# charge_board_v4-5.net
KiCad netlist of a schematic drawn in EAGLE
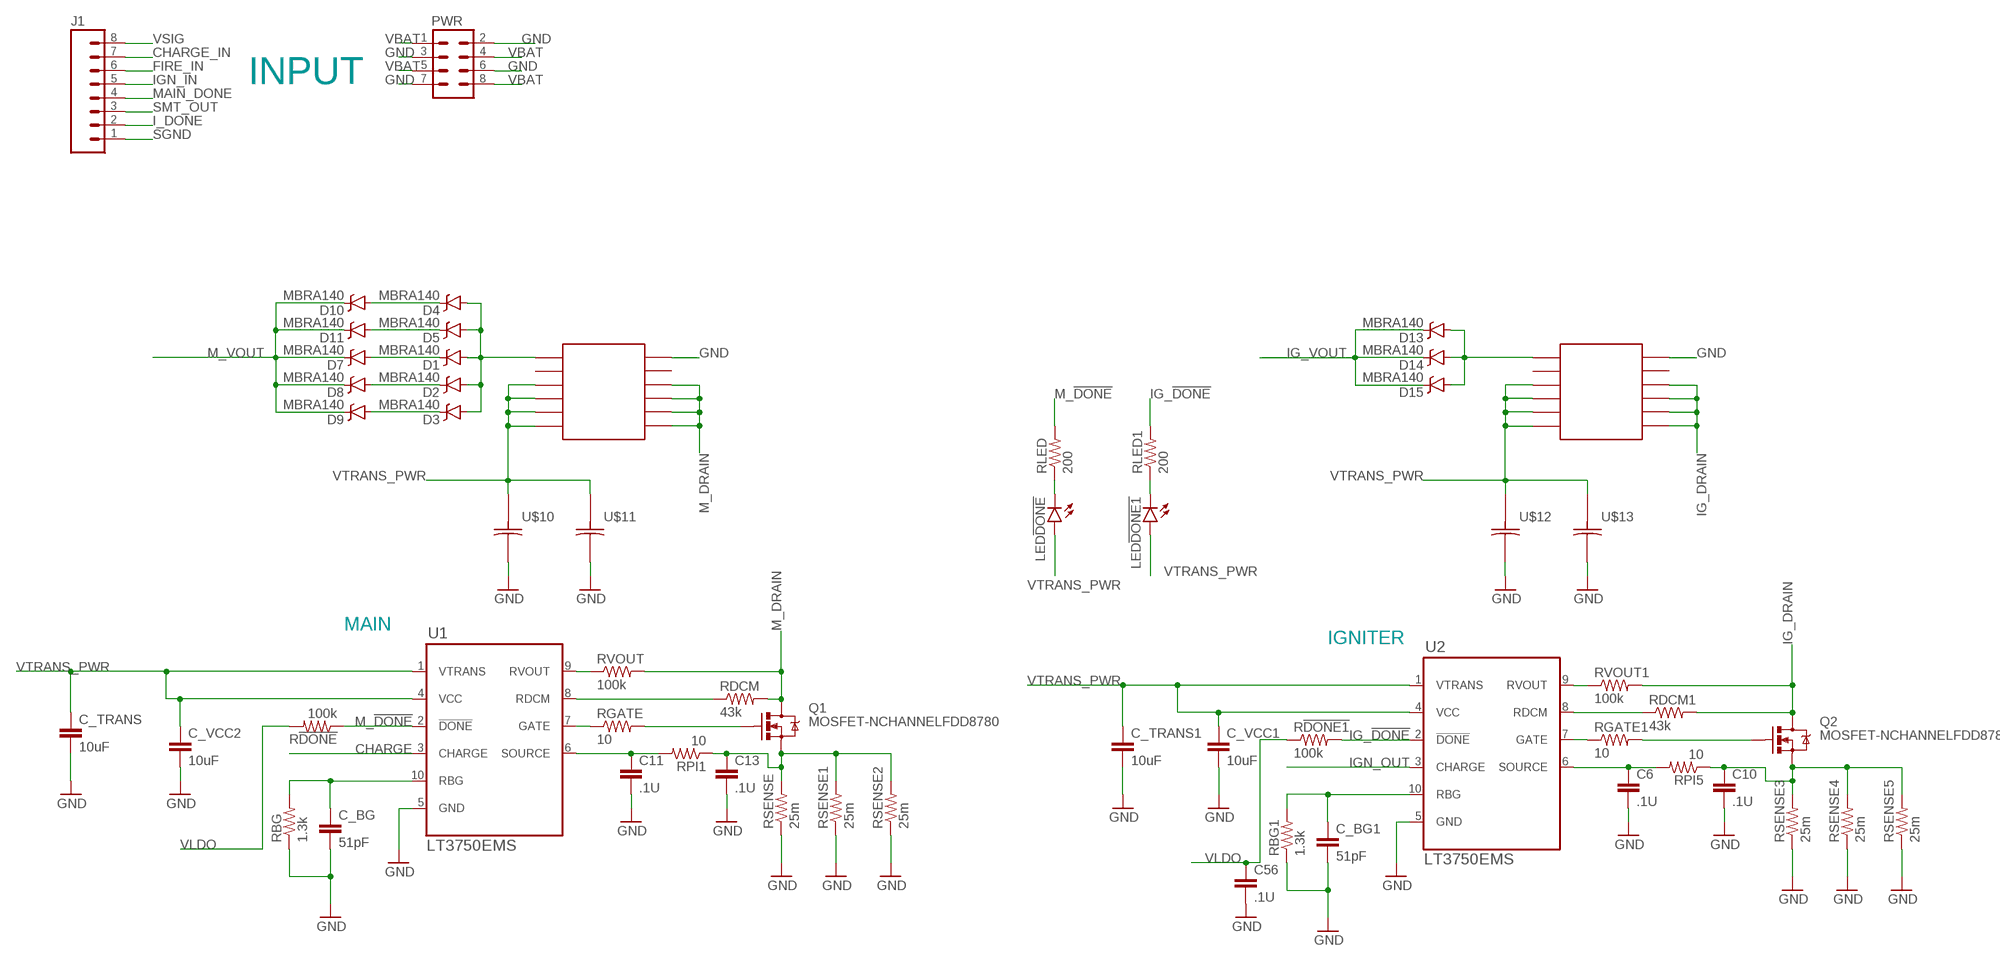
[diagram p0: schematic, sheet 1]
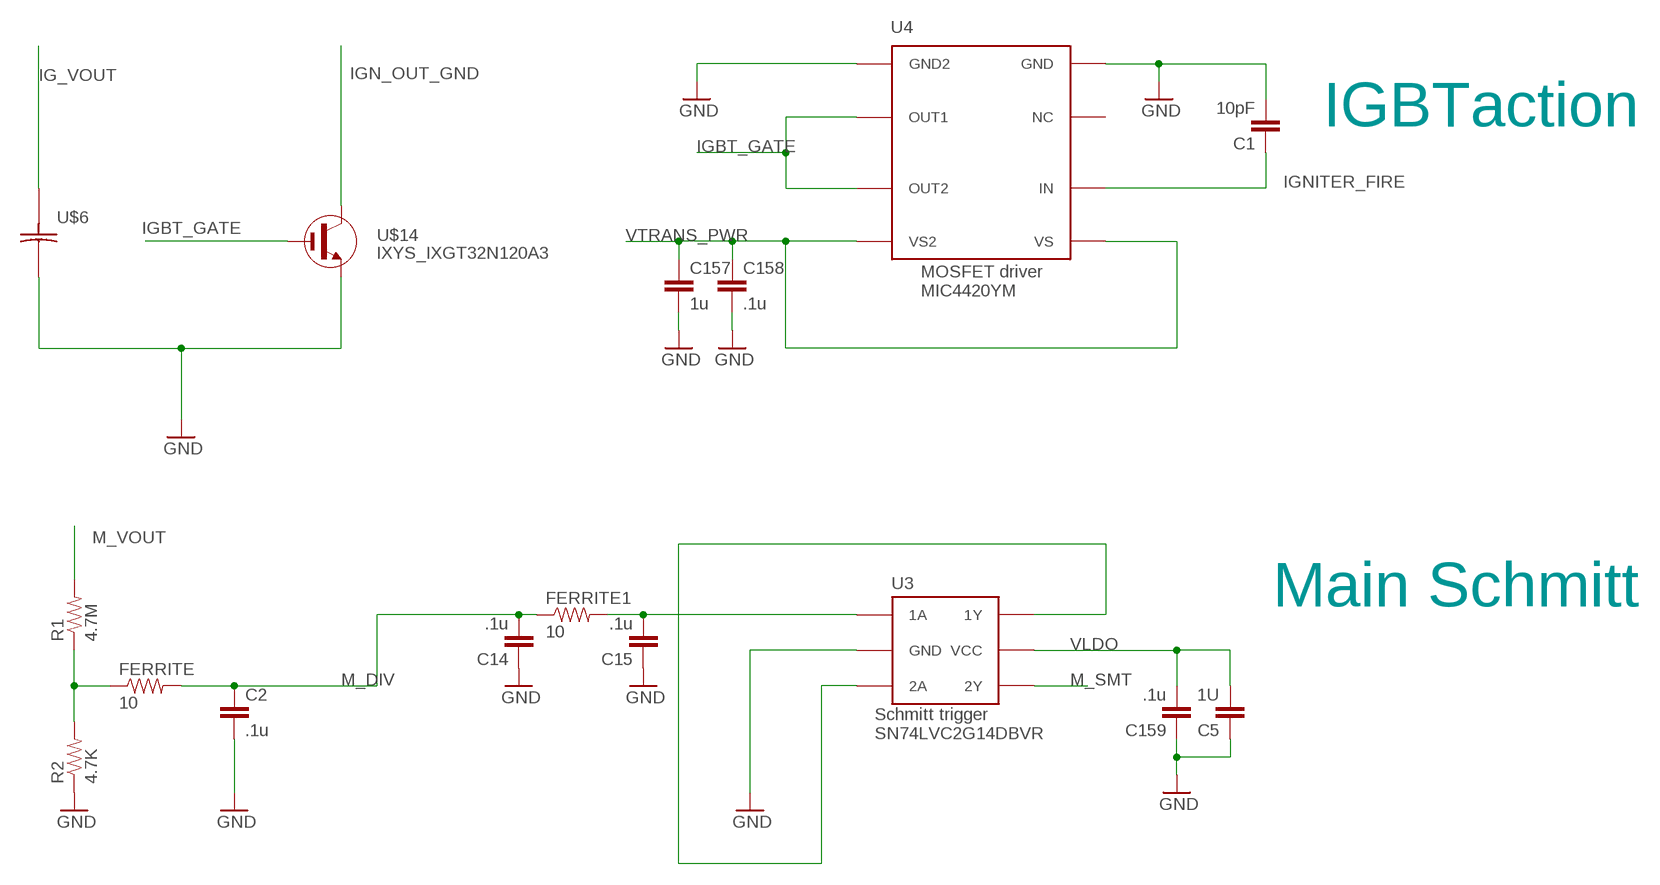
[diagram p1: schematic, sheet 2]
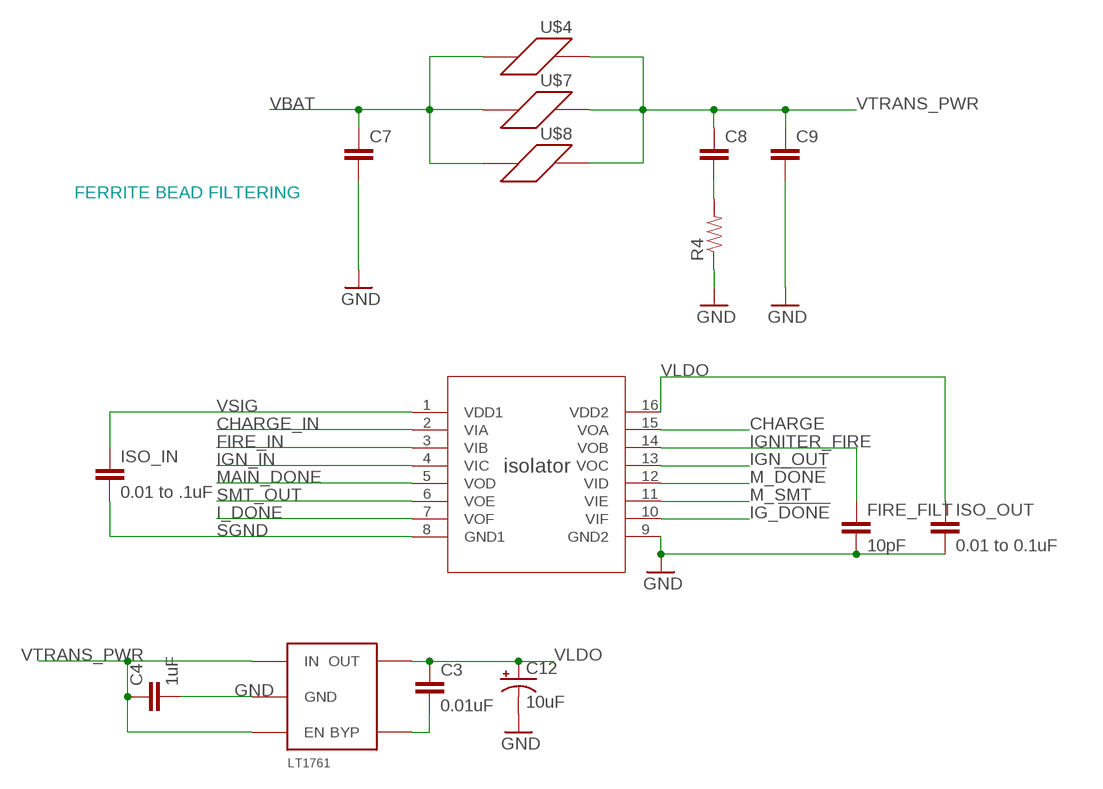
[diagram p2: schematic, sheet 3]

(export (version "E")
  (design (tool "Eeschema 10.0.6"))
  (components
    (comp (ref "C1")
      (value "10pF")
      (footprint "eagle-import:0805")
      (libsource (lib "eagle-import") (part "CAP0805"))
    )
    (comp (ref "C2")
      (value ".1u")
      (footprint "eagle-import:0805")
      (libsource (lib "eagle-import") (part "CAP0805"))
    )
    (comp (ref "C5")
      (value "1U")
      (footprint "eagle-import:0805")
      (libsource (lib "eagle-import") (part "CAP0805"))
    )
    (comp (ref "C14")
      (value ".1u")
      (footprint "eagle-import:0805")
      (libsource (lib "eagle-import") (part "CAP0805"))
    )
    (comp (ref "C15")
      (value ".1u")
      (footprint "eagle-import:0805")
      (libsource (lib "eagle-import") (part "CAP0805"))
    )
    (comp (ref "C157")
      (value "1u")
      (footprint "eagle-import:0805")
      (libsource (lib "eagle-import") (part "CAP0805"))
    )
    (comp (ref "C158")
      (value ".1u")
      (footprint "eagle-import:0805")
      (libsource (lib "eagle-import") (part "CAP0805"))
    )
    (comp (ref "C159")
      (value ".1u")
      (footprint "eagle-import:0805")
      (libsource (lib "eagle-import") (part "CAP0805"))
    )
    (comp (ref "FERRITE")
      (value "10")
      (footprint "eagle-import:0805")
      (libsource (lib "eagle-import") (part "RESISTOR0805-RES"))
    )
    (comp (ref "FERRITE1")
      (value "10")
      (footprint "eagle-import:0805")
      (libsource (lib "eagle-import") (part "RESISTOR0805-RES"))
    )
    (comp (ref "R1")
      (value "4.7M")
      (footprint "eagle-import:R2010")
      (libsource (lib "eagle-import") (part "RESISTOR2010"))
    )
    (comp (ref "R2")
      (value "4.7K")
      (footprint "eagle-import:R2010")
      (libsource (lib "eagle-import") (part "RESISTOR2010"))
    )
    (comp (ref "U$6")
      (value "KEMET_LDEQH3100KA5N00")
      (footprint "eagle-import:KEMET_F3078")
      (libsource (lib "eagle-import") (part "KEMET_LDEQH3100KA5N00"))
    )
    (comp (ref "U$14")
      (value "IXYS_IXGT32N120A3")
      (footprint "eagle-import:TO-268")
      (libsource (lib "eagle-import") (part "IXYS_IXGT32N120A3"))
    )
    (comp (ref "U3")
      (value "TI_SCHMITTRIGGER_SN74")
      (footprint "eagle-import:SOT-23-6")
      (libsource (lib "eagle-import") (part "TI_SCHMITTRIGGER_SN74"))
    )
    (comp (ref "U4")
      (value "MICREL_MOSFETDRIVER_MIC4420")
      (footprint "eagle-import:8-SOIC")
      (libsource (lib "eagle-import") (part "MICREL_MOSFETDRIVER_MIC4420"))
    )
    (comp (ref "ADUM163N")
      (value "ADUM163N1BRZ")
      (footprint "eagle-import:R_16")
      (libsource (lib "eagle-import") (part "ADUM163N1BRZ"))
    )
    (comp (ref "C3")
      (value "0.01uF")
      (footprint "eagle-import:0805")
      (libsource (lib "eagle-import") (part "SparkFun-Passives_CAP0805"))
    )
    (comp (ref "C4")
      (value "1uF")
      (footprint "eagle-import:0805")
      (libsource (lib "eagle-import") (part "SparkFun-Passives_CAP0805"))
    )
    (comp (ref "C7")
      (value "CAP0805")
      (footprint "eagle-import:0805")
      (libsource (lib "eagle-import") (part "CAP0805"))
    )
    (comp (ref "C8")
      (value "CAP0805")
      (footprint "eagle-import:0805")
      (libsource (lib "eagle-import") (part "CAP0805"))
    )
    (comp (ref "C9")
      (value "CAP0805")
      (footprint "eagle-import:0805")
      (libsource (lib "eagle-import") (part "CAP0805"))
    )
    (comp (ref "C12")
      (value "10uF")
      (footprint "eagle-import:EIA3216")
      (libsource (lib "eagle-import") (part "10UF-TANT"))
    )
    (comp (ref "FIRE_FILT")
      (value "10pF")
      (footprint "eagle-import:0805")
      (libsource (lib "eagle-import") (part "SparkFun-Passives_CAP0805"))
    )
    (comp (ref "ISO_IN")
      (value "0.01 to .1uF")
      (footprint "eagle-import:0805")
      (libsource (lib "eagle-import") (part "SparkFun-Passives_CAP0805"))
    )
    (comp (ref "ISO_OUT")
      (value "0.01 to 0.1uF")
      (footprint "eagle-import:0805")
      (libsource (lib "eagle-import") (part "SparkFun-Passives_CAP0805"))
    )
    (comp (ref "LDO")
      (value "LINEAR_LDO_LT1761-X")
      (footprint "eagle-import:SOT-23-5")
      (libsource (lib "eagle-import") (part "LINEAR_LDO_LT1761-X"))
    )
    (comp (ref "R4")
      (value "RESISTOR0805-RES")
      (footprint "eagle-import:0805")
      (libsource (lib "eagle-import") (part "RESISTOR0805-RES"))
    )
    (comp (ref "U$4")
      (value "B.L1_FBMJ2125HS420-T")
      (footprint "eagle-import:0805")
      (libsource (lib "eagle-import") (part "B.L1_FBMJ2125HS420-T"))
    )
    (comp (ref "U$7")
      (value "B.L2_FBMH1608HL121-T")
      (footprint "eagle-import:0603")
      (libsource (lib "eagle-import") (part "B.L2_FBMH1608HL121-T"))
    )
    (comp (ref "U$8")
      (value "I.L1_587-3855-1-ND")
      (footprint "eagle-import:1206")
      (libsource (lib "eagle-import") (part "I.L1_587-3855-1-ND"))
    )
    (comp (ref "C6")
      (value ".1U")
      (footprint "eagle-import:0805")
      (libsource (lib "eagle-import") (part "CAP0805"))
    )
    (comp (ref "C10")
      (value ".1U")
      (footprint "eagle-import:0805")
      (libsource (lib "eagle-import") (part "CAP0805"))
    )
    (comp (ref "C11")
      (value ".1U")
      (footprint "eagle-import:0805")
      (libsource (lib "eagle-import") (part "CAP0805"))
    )
    (comp (ref "C13")
      (value ".1U")
      (footprint "eagle-import:0805")
      (libsource (lib "eagle-import") (part "CAP0805"))
    )
    (comp (ref "C56")
      (value ".1U")
      (footprint "eagle-import:0805")
      (libsource (lib "eagle-import") (part "CAP0805"))
    )
    (comp (ref "C_BG")
      (value "51pF")
      (footprint "eagle-import:0805")
      (libsource (lib "eagle-import") (part "CAP0805"))
    )
    (comp (ref "C_BG1")
      (value "51pF")
      (footprint "eagle-import:0805")
      (libsource (lib "eagle-import") (part "CAP0805"))
    )
    (comp (ref "C_TRANS")
      (value "10uF")
      (footprint "eagle-import:0805")
      (libsource (lib "eagle-import") (part "CAP0805"))
    )
    (comp (ref "C_TRANS1")
      (value "10uF")
      (footprint "eagle-import:0805")
      (libsource (lib "eagle-import") (part "CAP0805"))
    )
    (comp (ref "C_VCC1")
      (value "10uF")
      (footprint "eagle-import:0805")
      (libsource (lib "eagle-import") (part "CAP0805"))
    )
    (comp (ref "C_VCC2")
      (value "10uF")
      (footprint "eagle-import:0805")
      (libsource (lib "eagle-import") (part "CAP0805"))
    )
    (comp (ref "D1")
      (value "MBRA140")
      (footprint "eagle-import:SMA-DIODE")
      (libsource (lib "eagle-import") (part "MBRA140"))
    )
    (comp (ref "D2")
      (value "MBRA140")
      (footprint "eagle-import:SMA-DIODE")
      (libsource (lib "eagle-import") (part "MBRA140"))
    )
    (comp (ref "D3")
      (value "MBRA140")
      (footprint "eagle-import:SMA-DIODE")
      (libsource (lib "eagle-import") (part "MBRA140"))
    )
    (comp (ref "D4")
      (value "MBRA140")
      (footprint "eagle-import:SMA-DIODE")
      (libsource (lib "eagle-import") (part "MBRA140"))
    )
    (comp (ref "D5")
      (value "MBRA140")
      (footprint "eagle-import:SMA-DIODE")
      (libsource (lib "eagle-import") (part "MBRA140"))
    )
    (comp (ref "D7")
      (value "MBRA140")
      (footprint "eagle-import:SMA-DIODE")
      (libsource (lib "eagle-import") (part "MBRA140"))
    )
    (comp (ref "D8")
      (value "MBRA140")
      (footprint "eagle-import:SMA-DIODE")
      (libsource (lib "eagle-import") (part "MBRA140"))
    )
    (comp (ref "D9")
      (value "MBRA140")
      (footprint "eagle-import:SMA-DIODE")
      (libsource (lib "eagle-import") (part "MBRA140"))
    )
    (comp (ref "D10")
      (value "MBRA140")
      (footprint "eagle-import:SMA-DIODE")
      (libsource (lib "eagle-import") (part "MBRA140"))
    )
    (comp (ref "D11")
      (value "MBRA140")
      (footprint "eagle-import:SMA-DIODE")
      (libsource (lib "eagle-import") (part "MBRA140"))
    )
    (comp (ref "D13")
      (value "MBRA140")
      (footprint "eagle-import:SMA-DIODE")
      (libsource (lib "eagle-import") (part "MBRA140"))
    )
    (comp (ref "D14")
      (value "MBRA140")
      (footprint "eagle-import:SMA-DIODE")
      (libsource (lib "eagle-import") (part "MBRA140"))
    )
    (comp (ref "D15")
      (value "MBRA140")
      (footprint "eagle-import:SMA-DIODE")
      (libsource (lib "eagle-import") (part "MBRA140"))
    )
    (comp (ref "J1")
      (value "M08")
      (footprint "eagle-import:1X08_ROUND")
      (libsource (lib "eagle-import") (part "M08"))
    )
    (comp (ref "LED!DONE")
      (value "LED1206")
      (footprint "eagle-import:LED-1206")
      (libsource (lib "eagle-import") (part "LED1206"))
    )
    (comp (ref "LED!DONE1")
      (value "LED1206")
      (footprint "eagle-import:LED-1206")
      (libsource (lib "eagle-import") (part "LED1206"))
    )
    (comp (ref "PWR")
      (value "M04X2")
      (footprint "eagle-import:2X4")
      (libsource (lib "eagle-import") (part "M04X2"))
    )
    (comp (ref "Q1")
      (value "MOSFET-NCHANNELFDD8780")
      (footprint "eagle-import:DPAK")
      (libsource (lib "eagle-import") (part "MOSFET-NCHANNELFDD8780"))
    )
    (comp (ref "Q2")
      (value "MOSFET-NCHANNELFDD8780")
      (footprint "eagle-import:DPAK")
      (libsource (lib "eagle-import") (part "MOSFET-NCHANNELFDD8780"))
    )
    (comp (ref "R!DONE")
      (value "100k")
      (footprint "eagle-import:0805")
      (libsource (lib "eagle-import") (part "SparkFun-Resistors_RESISTOR0805-RES"))
    )
    (comp (ref "R!DONE1")
      (value "100k")
      (footprint "eagle-import:0805")
      (libsource (lib "eagle-import") (part "SparkFun-Resistors_RESISTOR0805-RES"))
    )
    (comp (ref "RBG")
      (value "1.3k")
      (footprint "eagle-import:0805")
      (libsource (lib "eagle-import") (part "SparkFun-Resistors_RESISTOR0805-RES"))
    )
    (comp (ref "RBG1")
      (value "1.3k")
      (footprint "eagle-import:0805")
      (libsource (lib "eagle-import") (part "SparkFun-Resistors_RESISTOR0805-RES"))
    )
    (comp (ref "RDCM")
      (value "43k")
      (footprint "eagle-import:0805")
      (libsource (lib "eagle-import") (part "SparkFun-Resistors_RESISTOR0805-RES"))
    )
    (comp (ref "RDCM1")
      (value "43k")
      (footprint "eagle-import:0805")
      (libsource (lib "eagle-import") (part "SparkFun-Resistors_RESISTOR0805-RES"))
    )
    (comp (ref "RGATE")
      (value "10")
      (footprint "eagle-import:0805")
      (libsource (lib "eagle-import") (part "SparkFun-Resistors_RESISTOR0805-RES"))
    )
    (comp (ref "RGATE1")
      (value "10")
      (footprint "eagle-import:0805")
      (libsource (lib "eagle-import") (part "SparkFun-Resistors_RESISTOR0805-RES"))
    )
    (comp (ref "RLED")
      (value "200")
      (footprint "eagle-import:0805")
      (libsource (lib "eagle-import") (part "RESISTOR0805-RES"))
    )
    (comp (ref "RLED1")
      (value "200")
      (footprint "eagle-import:0805")
      (libsource (lib "eagle-import") (part "RESISTOR0805-RES"))
    )
    (comp (ref "RPI1")
      (value "10")
      (footprint "eagle-import:0805")
      (libsource (lib "eagle-import") (part "SparkFun-Resistors_RESISTOR0805-RES"))
    )
    (comp (ref "RPI5")
      (value "10")
      (footprint "eagle-import:0805")
      (libsource (lib "eagle-import") (part "SparkFun-Resistors_RESISTOR0805-RES"))
    )
    (comp (ref "RSENSE")
      (value "25m")
      (footprint "eagle-import:0805")
      (libsource (lib "eagle-import") (part "SparkFun-Resistors_RESISTOR0805-RES"))
    )
    (comp (ref "RSENSE1")
      (value "25m")
      (footprint "eagle-import:0805")
      (libsource (lib "eagle-import") (part "SparkFun-Resistors_RESISTOR0805-RES"))
    )
    (comp (ref "RSENSE2")
      (value "25m")
      (footprint "eagle-import:0805")
      (libsource (lib "eagle-import") (part "SparkFun-Resistors_RESISTOR0805-RES"))
    )
    (comp (ref "RSENSE3")
      (value "25m")
      (footprint "eagle-import:0805")
      (libsource (lib "eagle-import") (part "SparkFun-Resistors_RESISTOR0805-RES"))
    )
    (comp (ref "RSENSE4")
      (value "25m")
      (footprint "eagle-import:0805")
      (libsource (lib "eagle-import") (part "SparkFun-Resistors_RESISTOR0805-RES"))
    )
    (comp (ref "RSENSE5")
      (value "25m")
      (footprint "eagle-import:0805")
      (libsource (lib "eagle-import") (part "SparkFun-Resistors_RESISTOR0805-RES"))
    )
    (comp (ref "RVOUT")
      (value "100k")
      (footprint "eagle-import:0805")
      (libsource (lib "eagle-import") (part "SparkFun-Resistors_RESISTOR0805-RES"))
    )
    (comp (ref "RVOUT1")
      (value "100k")
      (footprint "eagle-import:0805")
      (libsource (lib "eagle-import") (part "SparkFun-Resistors_RESISTOR0805-RES"))
    )
    (comp (ref "U$1")
      (value "COILCRAFT_DA2034")
      (footprint "eagle-import:DA2034")
      (libsource (lib "eagle-import") (part "COILCRAFT_DA2034"))
    )
    (comp (ref "U$2")
      (value "COILCRAFT_DA2033")
      (footprint "eagle-import:DA2033")
      (libsource (lib "eagle-import") (part "COILCRAFT_DA2033"))
    )
    (comp (ref "U$10")
      (value "PANASONIC_16SVPG270M")
      (footprint "eagle-import:PANASONIC_SVPG")
      (libsource (lib "eagle-import") (part "PANASONIC_16SVPG270M"))
    )
    (comp (ref "U$11")
      (value "PANASONIC_16SVPG270M")
      (footprint "eagle-import:PANASONIC_SVPG")
      (libsource (lib "eagle-import") (part "PANASONIC_16SVPG270M"))
    )
    (comp (ref "U$12")
      (value "PANASONIC_16SVPG270M")
      (footprint "eagle-import:PANASONIC_SVPG")
      (libsource (lib "eagle-import") (part "PANASONIC_16SVPG270M"))
    )
    (comp (ref "U$13")
      (value "PANASONIC_16SVPG270M")
      (footprint "eagle-import:PANASONIC_SVPG")
      (libsource (lib "eagle-import") (part "PANASONIC_16SVPG270M"))
    )
    (comp (ref "U1")
      (value "LT3750EMS")
      (footprint "eagle-import:MSOP10")
      (libsource (lib "eagle-import") (part "LT3750EMS"))
    )
    (comp (ref "U2")
      (value "LT3750EMS")
      (footprint "eagle-import:MSOP10")
      (libsource (lib "eagle-import") (part "LT3750EMS"))
    )
  )
  (nets
    (net (code "1") (name "CHARGE") (class "Default")
      (node (ref "ADUM163N") (pin "15") (pinfunction "VOA_15") (pintype "passive"))
      (node (ref "U1") (pin "3") (pinfunction "CHARGE_3") (pintype "bidirectional"))
    )
    (net (code "2") (name "CHARGE_IN") (class "Default")
      (node (ref "ADUM163N") (pin "2") (pinfunction "VIA_2") (pintype "passive"))
      (node (ref "J1") (pin "7") (pinfunction "7_7") (pintype "passive"))
    )
    (net (code "3") (name "FIRE_IN") (class "Default")
      (node (ref "ADUM163N") (pin "3") (pinfunction "VIB_3") (pintype "passive"))
      (node (ref "J1") (pin "6") (pinfunction "6_6") (pintype "passive"))
    )
    (net (code "4") (name "GND") (class "Default")
      (node (ref "ADUM163N") (pin "9") (pinfunction "GND2_9") (pintype "passive"))
      (node (ref "C1") (pin "2") (pinfunction "2_2") (pintype "passive"))
      (node (ref "C10") (pin "2") (pinfunction "2_2") (pintype "passive"))
      (node (ref "C11") (pin "2") (pinfunction "2_2") (pintype "passive"))
      (node (ref "C12") (pin "C") (pinfunction "-_C") (pintype "passive"))
      (node (ref "C13") (pin "2") (pinfunction "2_2") (pintype "passive"))
      (node (ref "C14") (pin "1") (pinfunction "1_1") (pintype "passive"))
      (node (ref "C15") (pin "1") (pinfunction "1_1") (pintype "passive"))
      (node (ref "C157") (pin "2") (pinfunction "2_2") (pintype "passive"))
      (node (ref "C158") (pin "2") (pinfunction "2_2") (pintype "passive"))
      (node (ref "C159") (pin "1") (pinfunction "1_1") (pintype "passive"))
      (node (ref "C2") (pin "2") (pinfunction "2_2") (pintype "passive"))
      (node (ref "C4") (pin "2") (pinfunction "2_2") (pintype "passive"))
      (node (ref "C5") (pin "1") (pinfunction "1_1") (pintype "passive"))
      (node (ref "C56") (pin "2") (pinfunction "2_2") (pintype "passive"))
      (node (ref "C6") (pin "2") (pinfunction "2_2") (pintype "passive"))
      (node (ref "C7") (pin "2") (pinfunction "2_2") (pintype "passive"))
      (node (ref "C9") (pin "2") (pinfunction "2_2") (pintype "passive"))
      (node (ref "C_BG") (pin "2") (pinfunction "2_2") (pintype "passive"))
      (node (ref "C_BG1") (pin "2") (pinfunction "2_2") (pintype "passive"))
      (node (ref "C_TRANS") (pin "2") (pinfunction "2_2") (pintype "passive"))
      (node (ref "C_TRANS1") (pin "2") (pinfunction "2_2") (pintype "passive"))
      (node (ref "C_VCC1") (pin "2") (pinfunction "2_2") (pintype "passive"))
      (node (ref "C_VCC2") (pin "2") (pinfunction "2_2") (pintype "passive"))
      (node (ref "FIRE_FILT") (pin "2") (pinfunction "2_2") (pintype "passive"))
      (node (ref "ISO_OUT") (pin "2") (pinfunction "2_2") (pintype "passive"))
      (node (ref "LDO") (pin "P$2") (pinfunction "GND_P$2") (pintype "bidirectional"))
      (node (ref "PWR") (pin "2") (pinfunction "2_2") (pintype "passive"))
      (node (ref "PWR") (pin "3") (pinfunction "3_3") (pintype "passive"))
      (node (ref "PWR") (pin "6") (pinfunction "6_6") (pintype "passive"))
      (node (ref "PWR") (pin "7") (pinfunction "7_7") (pintype "passive"))
      (node (ref "R2") (pin "1") (pinfunction "1_1") (pintype "passive"))
      (node (ref "R4") (pin "1") (pinfunction "1_1") (pintype "passive"))
      (node (ref "RBG") (pin "1") (pinfunction "1_1") (pintype "passive"))
      (node (ref "RBG1") (pin "1") (pinfunction "1_1") (pintype "passive"))
      (node (ref "RSENSE") (pin "1") (pinfunction "1_1") (pintype "passive"))
      (node (ref "RSENSE1") (pin "1") (pinfunction "1_1") (pintype "passive"))
      (node (ref "RSENSE2") (pin "1") (pinfunction "1_1") (pintype "passive"))
      (node (ref "RSENSE3") (pin "1") (pinfunction "1_1") (pintype "passive"))
      (node (ref "RSENSE4") (pin "1") (pinfunction "1_1") (pintype "passive"))
      (node (ref "RSENSE5") (pin "1") (pinfunction "1_1") (pintype "passive"))
      (node (ref "U$1") (pin "P$12") (pinfunction "P$12_P$12") (pintype "bidirectional"))
      (node (ref "U$10") (pin "NEG") (pinfunction "NEG_NEG") (pintype "bidirectional"))
      (node (ref "U$11") (pin "NEG") (pinfunction "NEG_NEG") (pintype "bidirectional"))
      (node (ref "U$12") (pin "NEG") (pinfunction "NEG_NEG") (pintype "bidirectional"))
      (node (ref "U$13") (pin "NEG") (pinfunction "NEG_NEG") (pintype "bidirectional"))
      (node (ref "U$14") (pin "3") (pinfunction "E_3") (pintype "passive"))
      (node (ref "U$2") (pin "P$12") (pinfunction "P$12_P$12") (pintype "bidirectional"))
      (node (ref "U$6") (pin "NEG") (pinfunction "NEG_NEG") (pintype "bidirectional"))
      (node (ref "U1") (pin "5") (pinfunction "GND_5") (pintype "passive"))
      (node (ref "U2") (pin "5") (pinfunction "GND_5") (pintype "passive"))
      (node (ref "U3") (pin "P$2") (pinfunction "GND_P$2") (pintype "bidirectional"))
      (node (ref "U4") (pin "P$4") (pinfunction "GND_P$4") (pintype "bidirectional"))
      (node (ref "U4") (pin "P$5") (pinfunction "GND2_P$5") (pintype "bidirectional"))
    )
    (net (code "5") (name "IGBT_GATE") (class "Default")
      (node (ref "U$14") (pin "1") (pinfunction "G_1") (pintype "passive"))
      (node (ref "U4") (pin "P$6") (pinfunction "OUT1_P$6") (pintype "bidirectional"))
      (node (ref "U4") (pin "P$7") (pinfunction "OUT2_P$7") (pintype "bidirectional"))
    )
    (net (code "6") (name "IGNITER_FIRE") (class "Default")
      (node (ref "ADUM163N") (pin "14") (pinfunction "VOB_14") (pintype "passive"))
      (node (ref "C1") (pin "1") (pinfunction "1_1") (pintype "passive"))
      (node (ref "FIRE_FILT") (pin "1") (pinfunction "1_1") (pintype "passive"))
      (node (ref "U4") (pin "P$2") (pinfunction "IN_P$2") (pintype "bidirectional"))
    )
    (net (code "7") (name "IGN_IN") (class "Default")
      (node (ref "ADUM163N") (pin "4") (pinfunction "VIC_4") (pintype "passive"))
      (node (ref "J1") (pin "5") (pinfunction "5_5") (pintype "passive"))
    )
    (net (code "8") (name "IGN_OUT") (class "Default")
      (node (ref "ADUM163N") (pin "13") (pinfunction "VOC_13") (pintype "passive"))
      (node (ref "U2") (pin "3") (pinfunction "CHARGE_3") (pintype "bidirectional"))
    )
    (net (code "9") (name "IGN_OUT_GND") (class "Default")
      (node (ref "U$14") (pin "2") (pinfunction "C_2") (pintype "passive"))
    )
    (net (code "10") (name "IG_DRAIN") (class "Default")
      (node (ref "Q2") (pin "4") (pinfunction "D_4") (pintype "passive"))
      (node (ref "RDCM1") (pin "2") (pinfunction "2_2") (pintype "passive"))
      (node (ref "RVOUT1") (pin "2") (pinfunction "2_2") (pintype "passive"))
      (node (ref "U$2") (pin "P$10") (pinfunction "P$10_P$10") (pintype "bidirectional"))
      (node (ref "U$2") (pin "P$7") (pinfunction "P$7_P$7") (pintype "bidirectional"))
      (node (ref "U$2") (pin "P$8") (pinfunction "P$8_P$8") (pintype "bidirectional"))
      (node (ref "U$2") (pin "P$9") (pinfunction "P$9_P$9") (pintype "bidirectional"))
    )
    (net (code "11") (name "IG_VOUT") (class "Default")
      (node (ref "D13") (pin "C") (pinfunction "C_C") (pintype "passive"))
      (node (ref "D14") (pin "C") (pinfunction "C_C") (pintype "passive"))
      (node (ref "D15") (pin "C") (pinfunction "C_C") (pintype "passive"))
      (node (ref "U$6") (pin "POS") (pinfunction "POS_POS") (pintype "bidirectional"))
    )
    (net (code "12") (name "IG_~{DONE}") (class "Default")
      (node (ref "ADUM163N") (pin "10") (pinfunction "VIF_10") (pintype "passive"))
      (node (ref "R!DONE1") (pin "2") (pinfunction "2_2") (pintype "passive"))
      (node (ref "RLED1") (pin "2") (pinfunction "2_2") (pintype "passive"))
      (node (ref "U2") (pin "2") (pinfunction "~{DONE}_2") (pintype "bidirectional"))
    )
    (net (code "13") (name "I_DONE") (class "Default")
      (node (ref "ADUM163N") (pin "7") (pinfunction "VOF_7") (pintype "passive"))
      (node (ref "J1") (pin "2") (pinfunction "2_2") (pintype "passive"))
    )
    (net (code "14") (name "MAIN_DONE") (class "Default")
      (node (ref "ADUM163N") (pin "5") (pinfunction "VOD_5") (pintype "passive"))
      (node (ref "J1") (pin "4") (pinfunction "4_4") (pintype "passive"))
    )
    (net (code "15") (name "M_DIV") (class "Default")
      (node (ref "C14") (pin "2") (pinfunction "2_2") (pintype "passive"))
      (node (ref "C2") (pin "1") (pinfunction "1_1") (pintype "passive"))
      (node (ref "FERRITE") (pin "2") (pinfunction "2_2") (pintype "passive"))
      (node (ref "FERRITE1") (pin "1") (pinfunction "1_1") (pintype "passive"))
    )
    (net (code "16") (name "M_DRAIN") (class "Default")
      (node (ref "Q1") (pin "4") (pinfunction "D_4") (pintype "passive"))
      (node (ref "RDCM") (pin "2") (pinfunction "2_2") (pintype "passive"))
      (node (ref "RVOUT") (pin "2") (pinfunction "2_2") (pintype "passive"))
      (node (ref "U$1") (pin "P$10") (pinfunction "P$10_P$10") (pintype "bidirectional"))
      (node (ref "U$1") (pin "P$7") (pinfunction "P$7_P$7") (pintype "bidirectional"))
      (node (ref "U$1") (pin "P$8") (pinfunction "P$8_P$8") (pintype "bidirectional"))
      (node (ref "U$1") (pin "P$9") (pinfunction "P$9_P$9") (pintype "bidirectional"))
    )
    (net (code "17") (name "M_SMT") (class "Default")
      (node (ref "ADUM163N") (pin "11") (pinfunction "VIE_11") (pintype "passive"))
      (node (ref "U3") (pin "P$4") (pinfunction "2Y_P$4") (pintype "bidirectional"))
    )
    (net (code "18") (name "M_VOUT") (class "Default")
      (node (ref "D10") (pin "C") (pinfunction "C_C") (pintype "passive"))
      (node (ref "D11") (pin "C") (pinfunction "C_C") (pintype "passive"))
      (node (ref "D7") (pin "C") (pinfunction "C_C") (pintype "passive"))
      (node (ref "D8") (pin "C") (pinfunction "C_C") (pintype "passive"))
      (node (ref "D9") (pin "C") (pinfunction "C_C") (pintype "passive"))
      (node (ref "R1") (pin "2") (pinfunction "2_2") (pintype "passive"))
    )
    (net (code "19") (name "M_~{DONE}") (class "Default")
      (node (ref "ADUM163N") (pin "12") (pinfunction "VID_12") (pintype "passive"))
      (node (ref "R!DONE") (pin "1") (pinfunction "1_1") (pintype "passive"))
      (node (ref "RLED") (pin "2") (pinfunction "2_2") (pintype "passive"))
      (node (ref "U1") (pin "2") (pinfunction "~{DONE}_2") (pintype "bidirectional"))
    )
    (net (code "20") (name "Net-(C8-Pad2)") (class "Default")
      (node (ref "C8") (pin "2") (pinfunction "2_2") (pintype "passive"))
      (node (ref "R4") (pin "2") (pinfunction "2_2") (pintype "passive"))
    )
    (net (code "21") (name "Net-(D1-PadA)") (class "Default")
      (node (ref "D1") (pin "A") (pinfunction "A_A") (pintype "passive"))
      (node (ref "D2") (pin "A") (pinfunction "A_A") (pintype "passive"))
      (node (ref "D3") (pin "A") (pinfunction "A_A") (pintype "passive"))
      (node (ref "D4") (pin "A") (pinfunction "A_A") (pintype "passive"))
      (node (ref "D5") (pin "A") (pinfunction "A_A") (pintype "passive"))
      (node (ref "U$1") (pin "P$1") (pinfunction "P$1_P$1") (pintype "bidirectional"))
    )
    (net (code "22") (name "Net-(D1-PadC)") (class "Default")
      (node (ref "D1") (pin "C") (pinfunction "C_C") (pintype "passive"))
      (node (ref "D7") (pin "A") (pinfunction "A_A") (pintype "passive"))
    )
    (net (code "23") (name "Net-(D2-PadC)") (class "Default")
      (node (ref "D2") (pin "C") (pinfunction "C_C") (pintype "passive"))
      (node (ref "D8") (pin "A") (pinfunction "A_A") (pintype "passive"))
    )
    (net (code "24") (name "Net-(D3-PadC)") (class "Default")
      (node (ref "D3") (pin "C") (pinfunction "C_C") (pintype "passive"))
      (node (ref "D9") (pin "A") (pinfunction "A_A") (pintype "passive"))
    )
    (net (code "25") (name "Net-(D10-PadA)") (class "Default")
      (node (ref "D10") (pin "A") (pinfunction "A_A") (pintype "passive"))
      (node (ref "D4") (pin "C") (pinfunction "C_C") (pintype "passive"))
    )
    (net (code "26") (name "Net-(D11-PadA)") (class "Default")
      (node (ref "D11") (pin "A") (pinfunction "A_A") (pintype "passive"))
      (node (ref "D5") (pin "C") (pinfunction "C_C") (pintype "passive"))
    )
    (net (code "27") (name "Net-(D13-PadA)") (class "Default")
      (node (ref "D13") (pin "A") (pinfunction "A_A") (pintype "passive"))
      (node (ref "D14") (pin "A") (pinfunction "A_A") (pintype "passive"))
      (node (ref "D15") (pin "A") (pinfunction "A_A") (pintype "passive"))
      (node (ref "U$2") (pin "P$1") (pinfunction "P$1_P$1") (pintype "bidirectional"))
    )
    (net (code "28") (name "Net-(FERRITE-Pad1)") (class "Default")
      (node (ref "FERRITE") (pin "1") (pinfunction "1_1") (pintype "passive"))
      (node (ref "R1") (pin "1") (pinfunction "1_1") (pintype "passive"))
      (node (ref "R2") (pin "2") (pinfunction "2_2") (pintype "passive"))
    )
    (net (code "29") (name "Net-(LDO-BYP)") (class "Default")
      (node (ref "C3") (pin "2") (pinfunction "2_2") (pintype "passive"))
      (node (ref "LDO") (pin "P$4") (pinfunction "BYP_P$4") (pintype "bidirectional"))
    )
    (net (code "30") (name "Net-(LED!DONE-PadC)") (class "Default")
      (node (ref "LED!DONE") (pin "C") (pinfunction "C_C") (pintype "passive"))
      (node (ref "RLED") (pin "1") (pinfunction "1_1") (pintype "passive"))
    )
    (net (code "31") (name "Net-(LED!DONE1-PadC)") (class "Default")
      (node (ref "LED!DONE1") (pin "C") (pinfunction "C_C") (pintype "passive"))
      (node (ref "RLED1") (pin "1") (pinfunction "1_1") (pintype "passive"))
    )
    (net (code "32") (name "Net-(Q1-G)") (class "Default")
      (node (ref "Q1") (pin "1") (pinfunction "G_1") (pintype "passive"))
      (node (ref "RGATE") (pin "2") (pinfunction "2_2") (pintype "passive"))
    )
    (net (code "33") (name "Net-(Q1-S)") (class "Default")
      (node (ref "C13") (pin "1") (pinfunction "1_1") (pintype "passive"))
      (node (ref "Q1") (pin "3") (pinfunction "S_3") (pintype "passive"))
      (node (ref "RPI1") (pin "1") (pinfunction "1_1") (pintype "passive"))
      (node (ref "RSENSE") (pin "2") (pinfunction "2_2") (pintype "passive"))
      (node (ref "RSENSE1") (pin "2") (pinfunction "2_2") (pintype "passive"))
      (node (ref "RSENSE2") (pin "2") (pinfunction "2_2") (pintype "passive"))
    )
    (net (code "34") (name "Net-(Q2-G)") (class "Default")
      (node (ref "Q2") (pin "1") (pinfunction "G_1") (pintype "passive"))
      (node (ref "RGATE1") (pin "2") (pinfunction "2_2") (pintype "passive"))
    )
    (net (code "35") (name "Net-(Q2-S)") (class "Default")
      (node (ref "C10") (pin "1") (pinfunction "1_1") (pintype "passive"))
      (node (ref "Q2") (pin "3") (pinfunction "S_3") (pintype "passive"))
      (node (ref "RPI5") (pin "1") (pinfunction "1_1") (pintype "passive"))
      (node (ref "RSENSE3") (pin "2") (pinfunction "2_2") (pintype "passive"))
      (node (ref "RSENSE4") (pin "2") (pinfunction "2_2") (pintype "passive"))
      (node (ref "RSENSE5") (pin "2") (pinfunction "2_2") (pintype "passive"))
    )
    (net (code "36") (name "Net-(U1-GATE)") (class "Default")
      (node (ref "RGATE") (pin "1") (pinfunction "1_1") (pintype "passive"))
      (node (ref "U1") (pin "7") (pinfunction "GATE_7") (pintype "bidirectional"))
    )
    (net (code "37") (name "Net-(U1-RBG)") (class "Default")
      (node (ref "C_BG") (pin "1") (pinfunction "1_1") (pintype "passive"))
      (node (ref "RBG") (pin "2") (pinfunction "2_2") (pintype "passive"))
      (node (ref "U1") (pin "10") (pinfunction "RBG_10") (pintype "output"))
    )
    (net (code "38") (name "Net-(U1-RDCM)") (class "Default")
      (node (ref "RDCM") (pin "1") (pinfunction "1_1") (pintype "passive"))
      (node (ref "U1") (pin "8") (pinfunction "RDCM_8") (pintype "input"))
    )
    (net (code "39") (name "Net-(U1-RVOUT)") (class "Default")
      (node (ref "RVOUT") (pin "1") (pinfunction "1_1") (pintype "passive"))
      (node (ref "U1") (pin "9") (pinfunction "RVOUT_9") (pintype "output"))
    )
    (net (code "40") (name "Net-(U1-SOURCE)") (class "Default")
      (node (ref "C11") (pin "1") (pinfunction "1_1") (pintype "passive"))
      (node (ref "RPI1") (pin "2") (pinfunction "2_2") (pintype "passive"))
      (node (ref "U1") (pin "6") (pinfunction "SOURCE_6") (pintype "input"))
    )
    (net (code "41") (name "Net-(U2-GATE)") (class "Default")
      (node (ref "RGATE1") (pin "1") (pinfunction "1_1") (pintype "passive"))
      (node (ref "U2") (pin "7") (pinfunction "GATE_7") (pintype "bidirectional"))
    )
    (net (code "42") (name "Net-(U2-RBG)") (class "Default")
      (node (ref "C_BG1") (pin "1") (pinfunction "1_1") (pintype "passive"))
      (node (ref "RBG1") (pin "2") (pinfunction "2_2") (pintype "passive"))
      (node (ref "U2") (pin "10") (pinfunction "RBG_10") (pintype "output"))
    )
    (net (code "43") (name "Net-(U2-RDCM)") (class "Default")
      (node (ref "RDCM1") (pin "1") (pinfunction "1_1") (pintype "passive"))
      (node (ref "U2") (pin "8") (pinfunction "RDCM_8") (pintype "input"))
    )
    (net (code "44") (name "Net-(U2-RVOUT)") (class "Default")
      (node (ref "RVOUT1") (pin "1") (pinfunction "1_1") (pintype "passive"))
      (node (ref "U2") (pin "9") (pinfunction "RVOUT_9") (pintype "output"))
    )
    (net (code "45") (name "Net-(U2-SOURCE)") (class "Default")
      (node (ref "C6") (pin "1") (pinfunction "1_1") (pintype "passive"))
      (node (ref "RPI5") (pin "2") (pinfunction "2_2") (pintype "passive"))
      (node (ref "U2") (pin "6") (pinfunction "SOURCE_6") (pintype "input"))
    )
    (net (code "46") (name "Net-(U3-1A)") (class "Default")
      (node (ref "C15") (pin "2") (pinfunction "2_2") (pintype "passive"))
      (node (ref "FERRITE1") (pin "2") (pinfunction "2_2") (pintype "passive"))
      (node (ref "U3") (pin "P$1") (pinfunction "1A_P$1") (pintype "bidirectional"))
    )
    (net (code "47") (name "Net-(U3-1Y)") (class "Default")
      (node (ref "U3") (pin "P$3") (pinfunction "2A_P$3") (pintype "bidirectional"))
      (node (ref "U3") (pin "P$6") (pinfunction "1Y_P$6") (pintype "bidirectional"))
    )
    (net (code "48") (name "SGND") (class "Default")
      (node (ref "ADUM163N") (pin "8") (pinfunction "GND1_8") (pintype "passive"))
      (node (ref "ISO_IN") (pin "2") (pinfunction "2_2") (pintype "passive"))
      (node (ref "J1") (pin "1") (pinfunction "1_1") (pintype "passive"))
    )
    (net (code "49") (name "SMT_OUT") (class "Default")
      (node (ref "ADUM163N") (pin "6") (pinfunction "VOE_6") (pintype "passive"))
      (node (ref "J1") (pin "3") (pinfunction "3_3") (pintype "passive"))
    )
    (net (code "50") (name "VBAT") (class "Default")
      (node (ref "C7") (pin "1") (pinfunction "1_1") (pintype "passive"))
      (node (ref "PWR") (pin "1") (pinfunction "1_1") (pintype "passive"))
      (node (ref "PWR") (pin "4") (pinfunction "4_4") (pintype "passive"))
      (node (ref "PWR") (pin "5") (pinfunction "5_5") (pintype "passive"))
      (node (ref "PWR") (pin "8") (pinfunction "8_8") (pintype "passive"))
      (node (ref "U$4") (pin "1") (pinfunction "P$1_1") (pintype "bidirectional"))
      (node (ref "U$7") (pin "1") (pinfunction "P$1_1") (pintype "bidirectional"))
      (node (ref "U$8") (pin "1") (pinfunction "P$1_1") (pintype "bidirectional"))
    )
    (net (code "51") (name "VLDO") (class "Default")
      (node (ref "ADUM163N") (pin "16") (pinfunction "VDD2_16") (pintype "passive"))
      (node (ref "C12") (pin "A") (pinfunction "+_A") (pintype "passive"))
      (node (ref "C159") (pin "2") (pinfunction "2_2") (pintype "passive"))
      (node (ref "C3") (pin "1") (pinfunction "1_1") (pintype "passive"))
      (node (ref "C5") (pin "2") (pinfunction "2_2") (pintype "passive"))
      (node (ref "C56") (pin "1") (pinfunction "1_1") (pintype "passive"))
      (node (ref "ISO_OUT") (pin "1") (pinfunction "1_1") (pintype "passive"))
      (node (ref "LDO") (pin "P$5") (pinfunction "OUT_P$5") (pintype "bidirectional"))
      (node (ref "R!DONE") (pin "2") (pinfunction "2_2") (pintype "passive"))
      (node (ref "R!DONE1") (pin "1") (pinfunction "1_1") (pintype "passive"))
      (node (ref "U3") (pin "P$5") (pinfunction "VCC_P$5") (pintype "bidirectional"))
    )
    (net (code "52") (name "VSIG") (class "Default")
      (node (ref "ADUM163N") (pin "1") (pinfunction "VDD1_1") (pintype "passive"))
      (node (ref "ISO_IN") (pin "1") (pinfunction "1_1") (pintype "passive"))
      (node (ref "J1") (pin "8") (pinfunction "8_8") (pintype "passive"))
    )
    (net (code "53") (name "VTRANS_PWR") (class "Default")
      (node (ref "C157") (pin "1") (pinfunction "1_1") (pintype "passive"))
      (node (ref "C158") (pin "1") (pinfunction "1_1") (pintype "passive"))
      (node (ref "C4") (pin "1") (pinfunction "1_1") (pintype "passive"))
      (node (ref "C8") (pin "1") (pinfunction "1_1") (pintype "passive"))
      (node (ref "C9") (pin "1") (pinfunction "1_1") (pintype "passive"))
      (node (ref "C_TRANS") (pin "1") (pinfunction "1_1") (pintype "passive"))
      (node (ref "C_TRANS1") (pin "1") (pinfunction "1_1") (pintype "passive"))
      (node (ref "C_VCC1") (pin "1") (pinfunction "1_1") (pintype "passive"))
      (node (ref "C_VCC2") (pin "1") (pinfunction "1_1") (pintype "passive"))
      (node (ref "LDO") (pin "P$1") (pinfunction "IN_P$1") (pintype "bidirectional"))
      (node (ref "LDO") (pin "P$3") (pinfunction "EN_P$3") (pintype "bidirectional"))
      (node (ref "LED!DONE") (pin "A") (pinfunction "A_A") (pintype "passive"))
      (node (ref "LED!DONE1") (pin "A") (pinfunction "A_A") (pintype "passive"))
      (node (ref "U$1") (pin "P$3") (pinfunction "P$3_P$3") (pintype "bidirectional"))
      (node (ref "U$1") (pin "P$4") (pinfunction "P$4_P$4") (pintype "bidirectional"))
      (node (ref "U$1") (pin "P$5") (pinfunction "P$5_P$5") (pintype "bidirectional"))
      (node (ref "U$1") (pin "P$6") (pinfunction "P$6_P$6") (pintype "bidirectional"))
      (node (ref "U$10") (pin "POS") (pinfunction "POS_POS") (pintype "bidirectional"))
      (node (ref "U$11") (pin "POS") (pinfunction "POS_POS") (pintype "bidirectional"))
      (node (ref "U$12") (pin "POS") (pinfunction "POS_POS") (pintype "bidirectional"))
      (node (ref "U$13") (pin "POS") (pinfunction "POS_POS") (pintype "bidirectional"))
      (node (ref "U$2") (pin "P$3") (pinfunction "P$3_P$3") (pintype "bidirectional"))
      (node (ref "U$2") (pin "P$4") (pinfunction "P$4_P$4") (pintype "bidirectional"))
      (node (ref "U$2") (pin "P$5") (pinfunction "P$5_P$5") (pintype "bidirectional"))
      (node (ref "U$2") (pin "P$6") (pinfunction "P$6_P$6") (pintype "bidirectional"))
      (node (ref "U$4") (pin "2") (pinfunction "P$2_2") (pintype "bidirectional"))
      (node (ref "U$7") (pin "2") (pinfunction "P$2_2") (pintype "bidirectional"))
      (node (ref "U$8") (pin "2") (pinfunction "P$2_2") (pintype "bidirectional"))
      (node (ref "U1") (pin "1") (pinfunction "VTRANS_1") (pintype "power_in"))
      (node (ref "U1") (pin "4") (pinfunction "VCC_4") (pintype "power_in"))
      (node (ref "U2") (pin "1") (pinfunction "VTRANS_1") (pintype "power_in"))
      (node (ref "U2") (pin "4") (pinfunction "VCC_4") (pintype "power_in"))
      (node (ref "U4") (pin "P$1") (pinfunction "VS_P$1") (pintype "bidirectional"))
      (node (ref "U4") (pin "P$8") (pinfunction "VS2_P$8") (pintype "bidirectional"))
    )
    (net (code "54") (name "unconnected-(U$1-PadP$2)") (class "Default")
      (node (ref "U$1") (pin "P$2") (pinfunction "P$2_P$2") (pintype "bidirectional"))
    )
    (net (code "55") (name "unconnected-(U$1-PadP$11)") (class "Default")
      (node (ref "U$1") (pin "P$11") (pinfunction "P$11_P$11") (pintype "bidirectional"))
    )
    (net (code "56") (name "unconnected-(U$2-PadP$2)") (class "Default")
      (node (ref "U$2") (pin "P$2") (pinfunction "P$2_P$2") (pintype "bidirectional"))
    )
    (net (code "57") (name "unconnected-(U$2-PadP$11)") (class "Default")
      (node (ref "U$2") (pin "P$11") (pinfunction "P$11_P$11") (pintype "bidirectional"))
    )
    (net (code "58") (name "unconnected-(U4-NC-PadP$3)") (class "Default")
      (node (ref "U4") (pin "P$3") (pinfunction "NC_P$3") (pintype "bidirectional"))
    )
  )
)
